# STLINK.net
KiCad netlist of a schematic drawn in Altium Designer
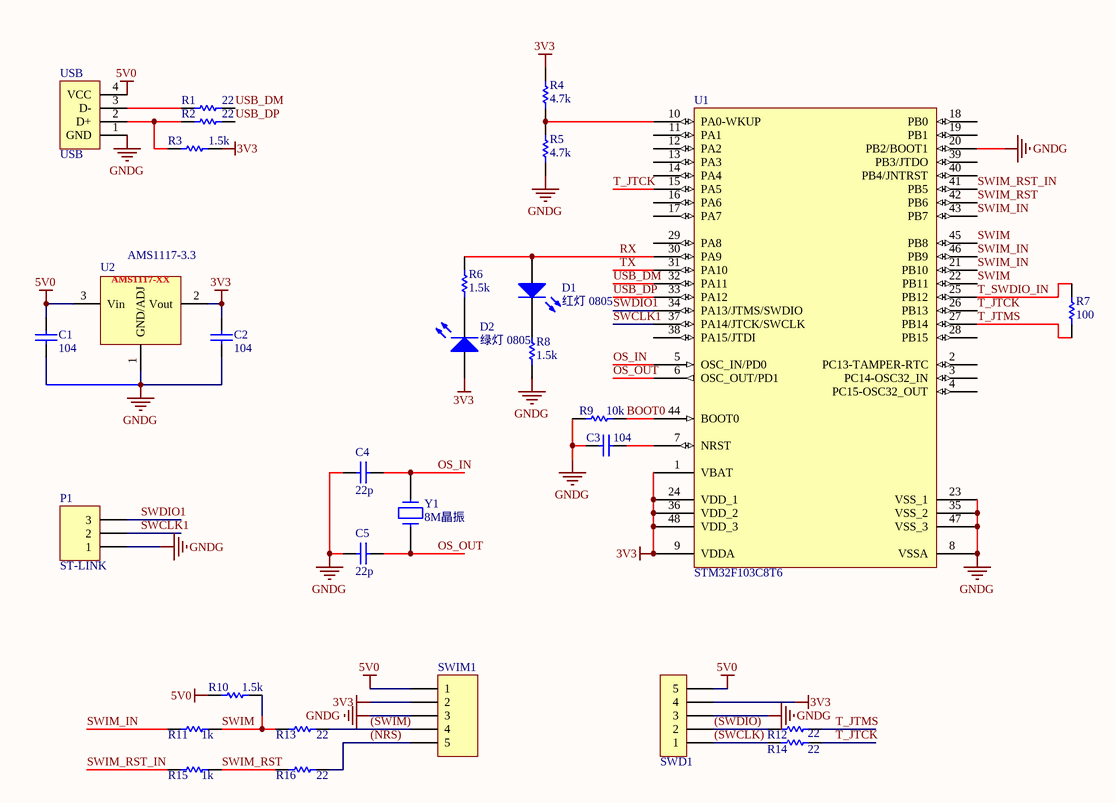
[diagram p0: STLINK.SchDoc]

(export (version "E")
  (design (tool "Eeschema 10.0.6"))
  (components
    (comp (ref "C1") (value "104") (footprint "C0805_L") (libsource (lib "WK_PCB") (part "Cap")))
    (comp (ref "C2") (value "104") (footprint "C0805_L") (libsource (lib "WK_PCB") (part "Cap")))
    (comp (ref "C3") (value "104") (footprint "C0805_L") (libsource (lib "WK_PCB") (part "Cap")))
    (comp (ref "C4")
      (value "22p")
      (footprint "C0805_L")
      (fields (field (name "Comment") "22pf"))
      (libsource (lib "WK_PCB") (part "Cap"))
    )
    (comp (ref "C5")
      (value "22p")
      (footprint "C0805_L")
      (fields (field (name "Comment") "22pf"))
      (libsource (lib "WK_PCB") (part "Cap"))
    )
    (comp (ref "D1")
      (value "红灯 0805")
      (footprint "LC-0805_LED_S1")
      (description "发光二极管")
      (libsource (lib "Miscellaneous Devices LC") (part "0805 蓝灯"))
    )
    (comp (ref "D2")
      (value "绿灯 0805")
      (footprint "LC-0805_LED_S1")
      (description "发光二极管")
      (libsource (lib "Miscellaneous Devices LC") (part "0805 蓝灯"))
    )
    (comp (ref "P1")
      (value "ST-LINK")
      (footprint "HDR1X3")
      (description "Header, 3-Pin")
      (fields (field (name "PUBLISHER") "Altium Limited"))
      (libsource (lib "Miscellaneous Connectors") (part "Header 3"))
    )
    (comp (ref "R1")
      (value "22")
      (footprint "0805_L")
      (fields (field (name "Comment") "22R"))
      (libsource (lib "WK_PCB") (part "RES"))
    )
    (comp (ref "R2")
      (value "22")
      (footprint "0805_L")
      (fields (field (name "Comment") "22R"))
      (libsource (lib "WK_PCB") (part "RES"))
    )
    (comp (ref "R3") (value "1.5k") (footprint "0805_L") (libsource (lib "WK_PCB") (part "RES")))
    (comp (ref "R4") (value "4.7k") (footprint "0805_L") (libsource (lib "WK_PCB") (part "RES")))
    (comp (ref "R5") (value "4.7k") (footprint "0805_L") (libsource (lib "WK_PCB") (part "RES")))
    (comp (ref "R6") (value "1.5k") (footprint "0805_L") (libsource (lib "WK_PCB") (part "RES")))
    (comp (ref "R7")
      (value "100")
      (footprint "0805_L")
      (fields (field (name "Comment") "100R"))
      (libsource (lib "WK_PCB") (part "RES"))
    )
    (comp (ref "R8") (value "1.5k") (footprint "0805_L") (libsource (lib "WK_PCB") (part "RES")))
    (comp (ref "R9") (value "10k") (footprint "0805_L") (libsource (lib "WK_PCB") (part "RES")))
    (comp (ref "R10") (value "1.5k") (footprint "0805_L") (libsource (lib "WK_PCB") (part "RES")))
    (comp (ref "R11") (value "1k") (footprint "0805_L") (libsource (lib "WK_PCB") (part "RES")))
    (comp (ref "R12")
      (value "22")
      (footprint "0805_L")
      (fields (field (name "Comment") "22R"))
      (libsource (lib "WK_PCB") (part "RES"))
    )
    (comp (ref "R13")
      (value "22")
      (footprint "0805_L")
      (fields (field (name "Comment") "22R"))
      (libsource (lib "WK_PCB") (part "RES"))
    )
    (comp (ref "R14")
      (value "22")
      (footprint "0805_L")
      (fields (field (name "Comment") "22R"))
      (libsource (lib "WK_PCB") (part "RES"))
    )
    (comp (ref "R15") (value "1k") (footprint "0805_L") (libsource (lib "WK_PCB") (part "RES")))
    (comp (ref "R16")
      (value "22")
      (footprint "0805_L")
      (fields (field (name "Comment") "22R"))
      (libsource (lib "WK_PCB") (part "RES"))
    )
    (comp (ref "SWD1") (value "Head5") (footprint "HEADER 5") (libsource (lib "WK_PCB") (part "HEAD 5")))
    (comp (ref "SWIM1")
      (value "Header 5")
      (footprint "HEADER 5")
      (description "Header, 5-Pin")
      (fields (field (name "PUBLISHER") "Altium Limited"))
      (libsource (lib "Miscellaneous Connectors") (part "Header 5"))
    )
    (comp (ref "U1")
      (value "STM32F103C8T6")
      (footprint "LQFP48_N")
      (description "STM32 ARM-based 32-bit MCU with 64 Kbytes Flash, 48-pin LQFP, Industrial Temperature")
      (fields (field (name "PUBLISHER") "Altium Limited"))
      (libsource (lib "ST Microcontroller 32-Bit STM32") (part "STM32F103C8T6"))
    )
    (comp (ref "U2")
      (value "AMS1117-3.3")
      (footprint "SOT-223")
      (description "AMS   800mA LOW DROPOUT VOLTAGE REGULATOR")
      (libsource (lib "电源管理") (part "AMS1117-XX"))
    )
    (comp (ref "USB") (value "USB") (footprint "USB_A_G") (libsource (lib "WK_PCB") (part "USB_G")))
    (comp (ref "Y1") (value "8M晶振") (footprint "XTAL_2") (libsource (lib "WK_PCB") (part "XTAL")))
  )
  (nets
    (net (code "1") (name "/(NRS)") (class "Default")
      (node (ref "R16") (pin "1") (pinfunction "1_1") (pintype "passive"))
      (node (ref "SWIM1") (pin "5") (pinfunction "5_5") (pintype "passive"))
    )
    (net (code "2") (name "/(SWCLK)") (class "Default")
      (node (ref "R14") (pin "1") (pinfunction "1_1") (pintype "passive"))
      (node (ref "SWD1") (pin "1") (pinfunction "1_1") (pintype "passive"))
    )
    (net (code "3") (name "/(SWDIO)") (class "Default")
      (node (ref "R12") (pin "1") (pinfunction "1_1") (pintype "passive"))
      (node (ref "SWD1") (pin "2") (pinfunction "2_2") (pintype "passive"))
    )
    (net (code "4") (name "/(SWIM)") (class "Default")
      (node (ref "R13") (pin "1") (pinfunction "1_1") (pintype "passive"))
      (node (ref "SWIM1") (pin "4") (pinfunction "4_4") (pintype "passive"))
    )
    (net (code "5") (name "/BOOT0") (class "Default")
      (node (ref "R9") (pin "2") (pinfunction "2_2") (pintype "passive"))
      (node (ref "U1") (pin "44") (pinfunction "BOOT0_44") (pintype "input"))
    )
    (net (code "6") (name "/OS_IN") (class "Default")
      (node (ref "C4") (pin "2") (pinfunction "2_2") (pintype "passive"))
      (node (ref "U1") (pin "5") (pinfunction "OSC_IN/PD0_5") (pintype "input"))
      (node (ref "Y1") (pin "2") (pinfunction "2_2") (pintype "passive"))
    )
    (net (code "7") (name "/OS_OUT") (class "Default")
      (node (ref "C5") (pin "2") (pinfunction "2_2") (pintype "passive"))
      (node (ref "U1") (pin "6") (pinfunction "OSC_OUT/PD1_6") (pintype "output"))
      (node (ref "Y1") (pin "1") (pinfunction "1_1") (pintype "passive"))
    )
    (net (code "8") (name "/RX") (class "Default")
      (node (ref "D1") (pin "A") (pinfunction "A_A") (pintype "passive"))
      (node (ref "R6") (pin "2") (pinfunction "2_2") (pintype "passive"))
      (node (ref "U1") (pin "30") (pinfunction "PA9_30") (pintype "bidirectional"))
    )
    (net (code "9") (name "/SWCLK1") (class "Default")
      (node (ref "P1") (pin "2") (pinfunction "2_2") (pintype "passive"))
      (node (ref "U1") (pin "37") (pinfunction "PA14/JTCK/SWCLK_37") (pintype "bidirectional"))
    )
    (net (code "10") (name "/SWDIO1") (class "Default")
      (node (ref "P1") (pin "3") (pinfunction "3_3") (pintype "passive"))
      (node (ref "U1") (pin "34") (pinfunction "PA13/JTMS/SWDIO_34") (pintype "bidirectional"))
    )
    (net (code "11") (name "/SWIM") (class "Default")
      (node (ref "R10") (pin "2") (pinfunction "2_2") (pintype "passive"))
      (node (ref "R11") (pin "2") (pinfunction "2_2") (pintype "passive"))
      (node (ref "R13") (pin "2") (pinfunction "2_2") (pintype "passive"))
      (node (ref "U1") (pin "22") (pinfunction "PB11_22") (pintype "bidirectional"))
      (node (ref "U1") (pin "45") (pinfunction "PB8_45") (pintype "bidirectional"))
    )
    (net (code "12") (name "/SWIM_IN") (class "Default")
      (node (ref "R11") (pin "1") (pinfunction "1_1") (pintype "passive"))
      (node (ref "U1") (pin "21") (pinfunction "PB10_21") (pintype "bidirectional"))
      (node (ref "U1") (pin "43") (pinfunction "PB7_43") (pintype "bidirectional"))
      (node (ref "U1") (pin "46") (pinfunction "PB9_46") (pintype "bidirectional"))
    )
    (net (code "13") (name "/SWIM_RST") (class "Default")
      (node (ref "R15") (pin "2") (pinfunction "2_2") (pintype "passive"))
      (node (ref "R16") (pin "2") (pinfunction "2_2") (pintype "passive"))
      (node (ref "U1") (pin "42") (pinfunction "PB6_42") (pintype "bidirectional"))
    )
    (net (code "14") (name "/SWIM_RST_IN") (class "Default")
      (node (ref "R15") (pin "1") (pinfunction "1_1") (pintype "passive"))
      (node (ref "U1") (pin "41") (pinfunction "PB5_41") (pintype "bidirectional"))
    )
    (net (code "15") (name "/TX") (class "Default")
      (node (ref "U1") (pin "31") (pinfunction "PA10_31") (pintype "bidirectional"))
    )
    (net (code "16") (name "/T_JTCK") (class "Default")
      (node (ref "R14") (pin "2") (pinfunction "2_2") (pintype "passive"))
      (node (ref "U1") (pin "15") (pinfunction "PA5_15") (pintype "bidirectional"))
      (node (ref "U1") (pin "26") (pinfunction "PB13_26") (pintype "bidirectional"))
    )
    (net (code "17") (name "/T_JTMS") (class "Default")
      (node (ref "R12") (pin "2") (pinfunction "2_2") (pintype "passive"))
      (node (ref "R7") (pin "1") (pinfunction "1_1") (pintype "passive"))
      (node (ref "U1") (pin "27") (pinfunction "PB14_27") (pintype "bidirectional"))
    )
    (net (code "18") (name "/T_SWDIO_IN") (class "Default")
      (node (ref "R7") (pin "2") (pinfunction "2_2") (pintype "passive"))
      (node (ref "U1") (pin "25") (pinfunction "PB12_25") (pintype "bidirectional"))
    )
    (net (code "19") (name "/USB_DM") (class "Default")
      (node (ref "R1") (pin "2") (pinfunction "2_2") (pintype "passive"))
      (node (ref "U1") (pin "32") (pinfunction "PA11_32") (pintype "bidirectional"))
    )
    (net (code "20") (name "/USB_DP") (class "Default")
      (node (ref "R2") (pin "2") (pinfunction "2_2") (pintype "passive"))
      (node (ref "U1") (pin "33") (pinfunction "PA12_33") (pintype "bidirectional"))
    )
    (net (code "21") (name "3V3") (class "Default")
      (node (ref "C2") (pin "2") (pinfunction "2_2") (pintype "passive"))
      (node (ref "D2") (pin "A") (pinfunction "A_A") (pintype "passive"))
      (node (ref "R3") (pin "2") (pinfunction "2_2") (pintype "passive"))
      (node (ref "R4") (pin "2") (pinfunction "2_2") (pintype "passive"))
      (node (ref "SWD1") (pin "4") (pinfunction "4_4") (pintype "passive"))
      (node (ref "SWIM1") (pin "2") (pinfunction "2_2") (pintype "passive"))
      (node (ref "U1") (pin "1") (pinfunction "VBAT_1") (pintype "power_in"))
      (node (ref "U1") (pin "24") (pinfunction "VDD_1_24") (pintype "power_in"))
      (node (ref "U1") (pin "36") (pinfunction "VDD_2_36") (pintype "power_in"))
      (node (ref "U1") (pin "48") (pinfunction "VDD_3_48") (pintype "power_in"))
      (node (ref "U1") (pin "9") (pinfunction "VDDA_9") (pintype "power_in"))
      (node (ref "U2") (pin "2") (pinfunction "Vout_2") (pintype "passive"))
    )
    (net (code "22") (name "5V0") (class "Default")
      (node (ref "C1") (pin "2") (pinfunction "2_2") (pintype "passive"))
      (node (ref "R10") (pin "1") (pinfunction "1_1") (pintype "passive"))
      (node (ref "SWD1") (pin "5") (pinfunction "5_5") (pintype "passive"))
      (node (ref "SWIM1") (pin "1") (pinfunction "1_1") (pintype "passive"))
      (node (ref "U2") (pin "3") (pinfunction "Vin_3") (pintype "passive"))
      (node (ref "USB") (pin "4") (pinfunction "VCC_4") (pintype "passive"))
    )
    (net (code "23") (name "GNDG") (class "Default")
      (node (ref "C1") (pin "1") (pinfunction "1_1") (pintype "passive"))
      (node (ref "C2") (pin "1") (pinfunction "1_1") (pintype "passive"))
      (node (ref "C3") (pin "1") (pinfunction "1_1") (pintype "passive"))
      (node (ref "C4") (pin "1") (pinfunction "1_1") (pintype "passive"))
      (node (ref "C5") (pin "1") (pinfunction "1_1") (pintype "passive"))
      (node (ref "P1") (pin "1") (pinfunction "1_1") (pintype "passive"))
      (node (ref "R5") (pin "1") (pinfunction "1_1") (pintype "passive"))
      (node (ref "R8") (pin "1") (pinfunction "1_1") (pintype "passive"))
      (node (ref "R9") (pin "1") (pinfunction "1_1") (pintype "passive"))
      (node (ref "SWD1") (pin "3") (pinfunction "3_3") (pintype "passive"))
      (node (ref "SWIM1") (pin "3") (pinfunction "3_3") (pintype "passive"))
      (node (ref "U1") (pin "20") (pinfunction "PB2/BOOT1_20") (pintype "bidirectional"))
      (node (ref "U1") (pin "23") (pinfunction "VSS_1_23") (pintype "power_in"))
      (node (ref "U1") (pin "35") (pinfunction "VSS_2_35") (pintype "power_in"))
      (node (ref "U1") (pin "47") (pinfunction "VSS_3_47") (pintype "power_in"))
      (node (ref "U1") (pin "8") (pinfunction "VSSA_8") (pintype "power_in"))
      (node (ref "U2") (pin "1") (pinfunction "GND/ADJ_1") (pintype "passive"))
      (node (ref "USB") (pin "1") (pinfunction "GND_1") (pintype "passive"))
    )
    (net (code "24") (name "Net-(D1-PadK)") (class "Default")
      (node (ref "D1") (pin "K") (pinfunction "K_K") (pintype "passive"))
      (node (ref "R8") (pin "2") (pinfunction "2_2") (pintype "passive"))
    )
    (net (code "25") (name "Net-(D2-PadK)") (class "Default")
      (node (ref "D2") (pin "K") (pinfunction "K_K") (pintype "passive"))
      (node (ref "R6") (pin "1") (pinfunction "1_1") (pintype "passive"))
    )
    (net (code "26") (name "Net-(U1-NRST)") (class "Default")
      (node (ref "C3") (pin "2") (pinfunction "2_2") (pintype "passive"))
      (node (ref "U1") (pin "7") (pinfunction "NRST_7") (pintype "bidirectional"))
    )
    (net (code "27") (name "Net-(U1-PA0-WKUP)") (class "Default")
      (node (ref "R4") (pin "1") (pinfunction "1_1") (pintype "passive"))
      (node (ref "R5") (pin "2") (pinfunction "2_2") (pintype "passive"))
      (node (ref "U1") (pin "10") (pinfunction "PA0-WKUP_10") (pintype "bidirectional"))
    )
    (net (code "28") (name "Net-(USB-D+)") (class "Default")
      (node (ref "R2") (pin "1") (pinfunction "1_1") (pintype "passive"))
      (node (ref "R3") (pin "1") (pinfunction "1_1") (pintype "passive"))
      (node (ref "USB") (pin "2") (pinfunction "D+_2") (pintype "passive"))
    )
    (net (code "29") (name "Net-(USB-D-)") (class "Default")
      (node (ref "R1") (pin "1") (pinfunction "1_1") (pintype "passive"))
      (node (ref "USB") (pin "3") (pinfunction "D-_3") (pintype "passive"))
    )
    (net (code "30") (name "unconnected-(U1-PA1-Pad11)") (class "Default")
      (node (ref "U1") (pin "11") (pinfunction "PA1_11") (pintype "bidirectional"))
    )
    (net (code "31") (name "unconnected-(U1-PA2-Pad12)") (class "Default")
      (node (ref "U1") (pin "12") (pinfunction "PA2_12") (pintype "bidirectional"))
    )
    (net (code "32") (name "unconnected-(U1-PA3-Pad13)") (class "Default")
      (node (ref "U1") (pin "13") (pinfunction "PA3_13") (pintype "bidirectional"))
    )
    (net (code "33") (name "unconnected-(U1-PA4-Pad14)") (class "Default")
      (node (ref "U1") (pin "14") (pinfunction "PA4_14") (pintype "bidirectional"))
    )
    (net (code "34") (name "unconnected-(U1-PA6-Pad16)") (class "Default")
      (node (ref "U1") (pin "16") (pinfunction "PA6_16") (pintype "bidirectional"))
    )
    (net (code "35") (name "unconnected-(U1-PA7-Pad17)") (class "Default")
      (node (ref "U1") (pin "17") (pinfunction "PA7_17") (pintype "bidirectional"))
    )
    (net (code "36") (name "unconnected-(U1-PA8-Pad29)") (class "Default")
      (node (ref "U1") (pin "29") (pinfunction "PA8_29") (pintype "bidirectional"))
    )
    (net (code "37") (name "unconnected-(U1-PA15{slash}JTDI-Pad38)") (class "Default")
      (node (ref "U1") (pin "38") (pinfunction "PA15/JTDI_38") (pintype "bidirectional"))
    )
    (net (code "38") (name "unconnected-(U1-PB0-Pad18)") (class "Default")
      (node (ref "U1") (pin "18") (pinfunction "PB0_18") (pintype "bidirectional"))
    )
    (net (code "39") (name "unconnected-(U1-PB1-Pad19)") (class "Default")
      (node (ref "U1") (pin "19") (pinfunction "PB1_19") (pintype "bidirectional"))
    )
    (net (code "40") (name "unconnected-(U1-PB3{slash}JTDO-Pad39)") (class "Default")
      (node (ref "U1") (pin "39") (pinfunction "PB3/JTDO_39") (pintype "bidirectional"))
    )
    (net (code "41") (name "unconnected-(U1-PB4{slash}JNTRST-Pad40)") (class "Default")
      (node (ref "U1") (pin "40") (pinfunction "PB4/JNTRST_40") (pintype "bidirectional"))
    )
    (net (code "42") (name "unconnected-(U1-PB15-Pad28)") (class "Default")
      (node (ref "U1") (pin "28") (pinfunction "PB15_28") (pintype "bidirectional"))
    )
    (net (code "43") (name "unconnected-(U1-PC13-TAMPER-RTC-Pad2)") (class "Default")
      (node (ref "U1") (pin "2") (pinfunction "PC13-TAMPER-RTC_2") (pintype "bidirectional"))
    )
    (net (code "44") (name "unconnected-(U1-PC14-OSC32_IN-Pad3)") (class "Default")
      (node (ref "U1") (pin "3") (pinfunction "PC14-OSC32_IN_3") (pintype "bidirectional"))
    )
    (net (code "45") (name "unconnected-(U1-PC15-OSC32_OUT-Pad4)") (class "Default")
      (node (ref "U1") (pin "4") (pinfunction "PC15-OSC32_OUT_4") (pintype "bidirectional"))
    )
  )
)
